# Picobot_10.net
KiCad netlist of a schematic drawn in EAGLE
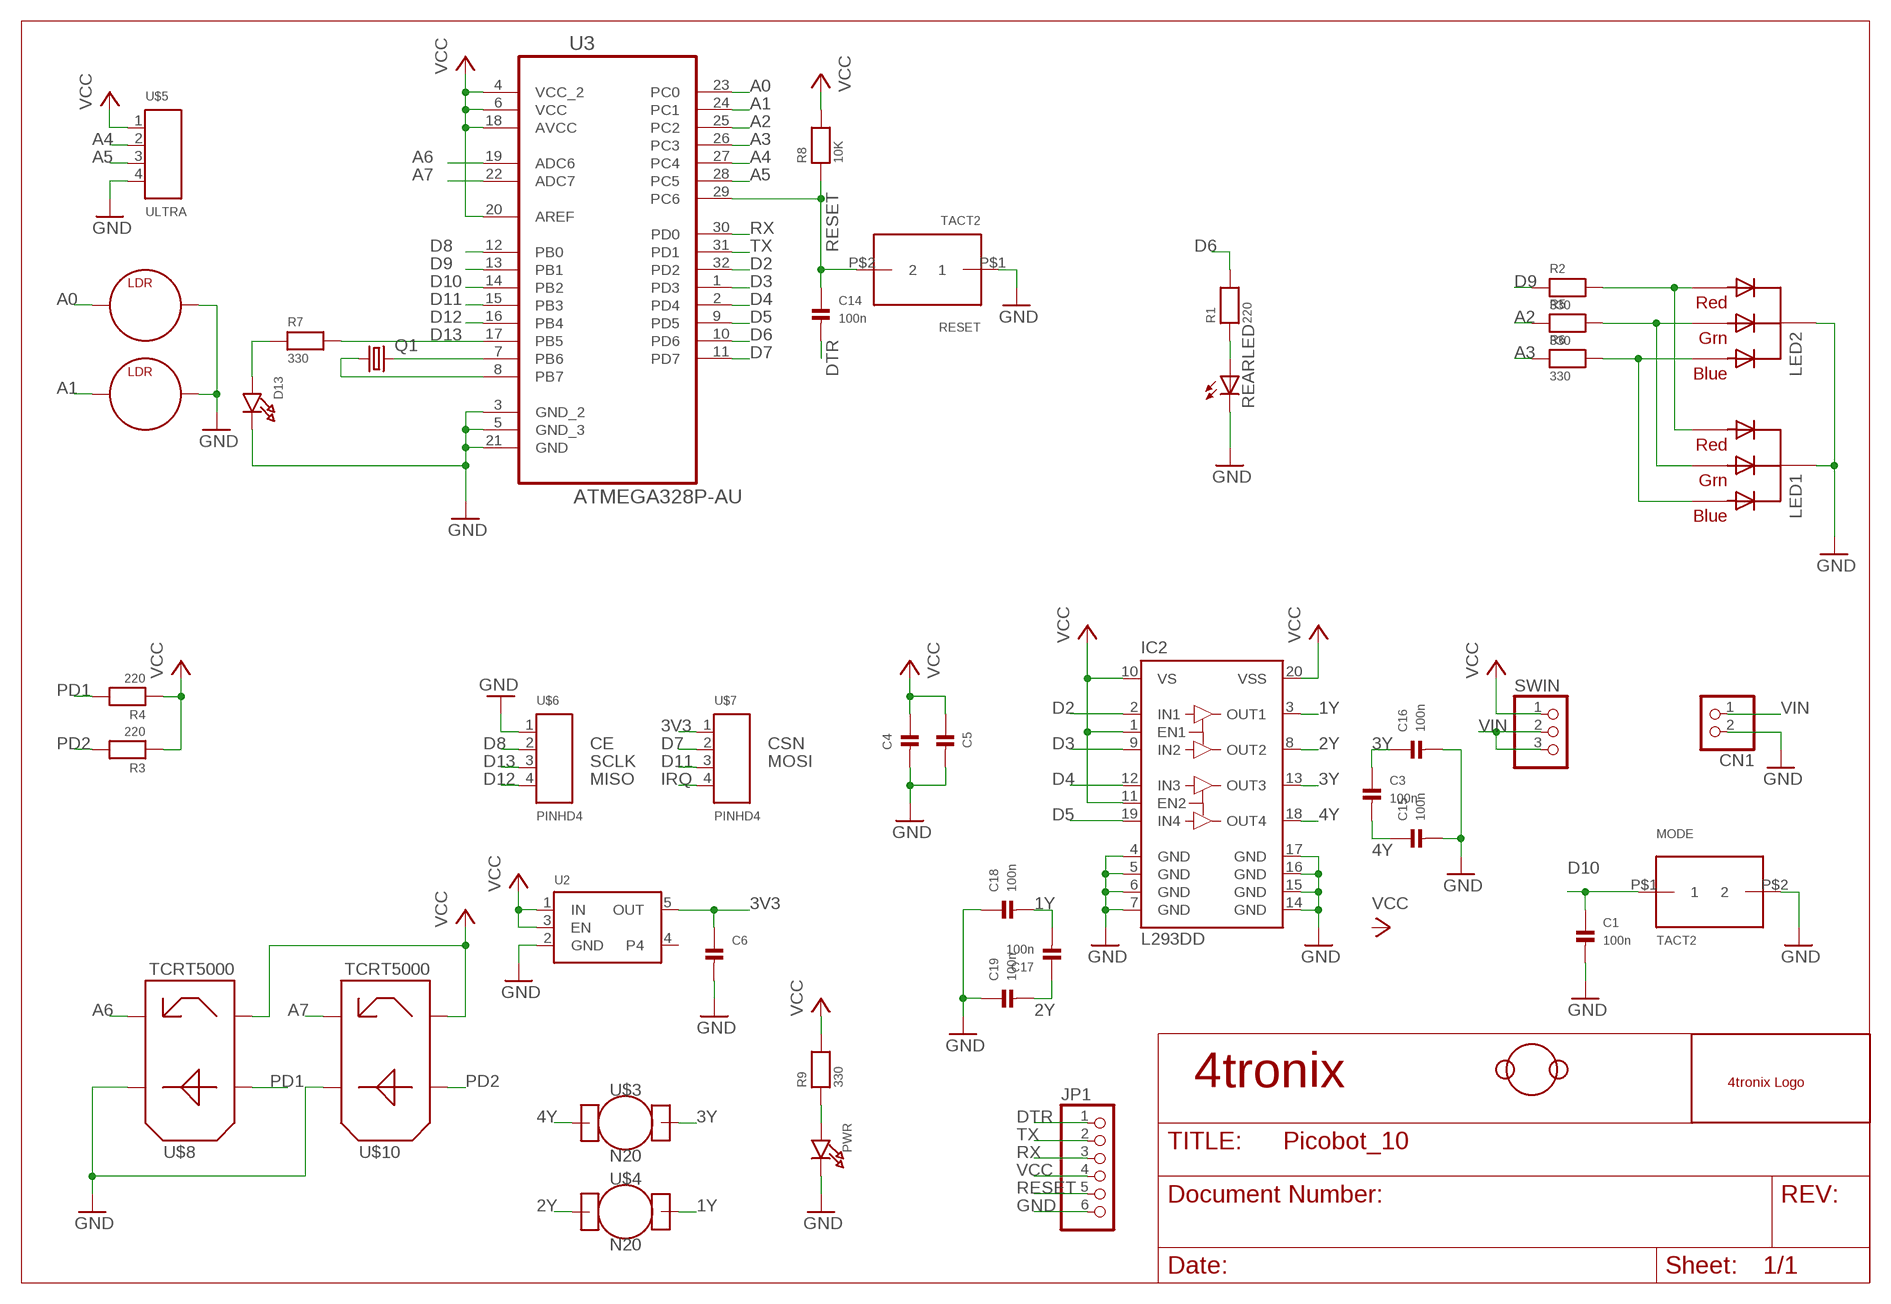
[diagram p0: schematic, sheet 1]

(export (version "E")
  (design (tool "Eeschema 10.0.6"))
  (components
    (comp (ref "C1")
      (value "100n")
      (footprint "eagle-import:_0805MP")
      (libsource (lib "eagle-import") (part "CAP_CERAMIC_0805MP"))
    )
    (comp (ref "C3")
      (value "100n")
      (footprint "eagle-import:_0805MP")
      (libsource (lib "eagle-import") (part "CAP_CERAMIC_0805MP"))
    )
    (comp (ref "C4")
      (value "CAP_CERAMIC_0805MP")
      (footprint "eagle-import:_0805MP")
      (libsource (lib "eagle-import") (part "CAP_CERAMIC_0805MP"))
    )
    (comp (ref "C5")
      (value "CAP_CERAMIC_0805MP")
      (footprint "eagle-import:_0805MP")
      (libsource (lib "eagle-import") (part "CAP_CERAMIC_0805MP"))
    )
    (comp (ref "C6")
      (value "CAP_CERAMIC_0805MP")
      (footprint "eagle-import:_0805MP")
      (libsource (lib "eagle-import") (part "CAP_CERAMIC_0805MP"))
    )
    (comp (ref "C14")
      (value "100n")
      (footprint "eagle-import:_0805MP")
      (libsource (lib "eagle-import") (part "CAP_CERAMIC_0805MP"))
    )
    (comp (ref "C15")
      (value "100n")
      (footprint "eagle-import:_0805MP")
      (libsource (lib "eagle-import") (part "CAP_CERAMIC_0805MP"))
    )
    (comp (ref "C16")
      (value "100n")
      (footprint "eagle-import:_0805MP")
      (libsource (lib "eagle-import") (part "CAP_CERAMIC_0805MP"))
    )
    (comp (ref "C17")
      (value "100n")
      (footprint "eagle-import:_0805MP")
      (libsource (lib "eagle-import") (part "CAP_CERAMIC_0805MP"))
    )
    (comp (ref "C18")
      (value "100n")
      (footprint "eagle-import:_0805MP")
      (libsource (lib "eagle-import") (part "CAP_CERAMIC_0805MP"))
    )
    (comp (ref "C19")
      (value "100n")
      (footprint "eagle-import:_0805MP")
      (libsource (lib "eagle-import") (part "CAP_CERAMIC_0805MP"))
    )
    (comp (ref "CN1")
      (value "JST_2PIN-THM")
      (footprint "eagle-import:JST-PH-2-THM")
      (libsource (lib "eagle-import") (part "JST_2PIN-THM"))
    )
    (comp (ref "D13")
      (value "LED0805_NOOUTLINE")
      (footprint "eagle-import:CHIPLED_0805_NOOUTLINE")
      (libsource (lib "eagle-import") (part "LED0805_NOOUTLINE"))
    )
    (comp (ref "IC2")
      (value "L293DD")
      (footprint "eagle-import:SO20")
      (libsource (lib "eagle-import") (part "L293DD"))
    )
    (comp (ref "JP1")
      (value "PINHD-1X6CB")
      (footprint "eagle-import:1X06-CLEANBIG")
      (libsource (lib "eagle-import") (part "PINHD-1X6CB"))
    )
    (comp (ref "LDR1")
      (value "LDR")
      (footprint "eagle-import:LDR")
      (libsource (lib "eagle-import") (part "LDR"))
    )
    (comp (ref "LDR2")
      (value "LDR")
      (footprint "eagle-import:LDR")
      (libsource (lib "eagle-import") (part "LDR"))
    )
    (comp (ref "LED1")
      (value "RGBLED_CA-5MM")
      (footprint "eagle-import:LED5MMRGB")
      (libsource (lib "eagle-import") (part "RGBLED_CA-5MM"))
    )
    (comp (ref "LED2")
      (value "RGBLED_CA-5MM")
      (footprint "eagle-import:LED5MMRGB")
      (libsource (lib "eagle-import") (part "RGBLED_CA-5MM"))
    )
    (comp (ref "MODE")
      (value "TACT2")
      (footprint "eagle-import:TACT2-PIN")
      (libsource (lib "eagle-import") (part "TACT2"))
    )
    (comp (ref "PWR")
      (value "LED0805_NOOUTLINE")
      (footprint "eagle-import:CHIPLED_0805_NOOUTLINE")
      (libsource (lib "eagle-import") (part "LED0805_NOOUTLINE"))
    )
    (comp (ref "Q1")
      (value "CRYSTALHC49S")
      (footprint "eagle-import:HC49_S")
      (libsource (lib "eagle-import") (part "CRYSTALHC49S"))
    )
    (comp (ref "R1")
      (value "220")
      (footprint "eagle-import:0805_NOTHERMALS")
      (libsource (lib "eagle-import") (part "RESISTOR0805_NOTHERMALS"))
    )
    (comp (ref "R2")
      (value "330")
      (footprint "eagle-import:0805_NOTHERMALS")
      (libsource (lib "eagle-import") (part "RESISTOR0805_NOTHERMALS"))
    )
    (comp (ref "R3")
      (value "220")
      (footprint "eagle-import:0805_NOTHERMALS")
      (libsource (lib "eagle-import") (part "RESISTOR0805_NOTHERMALS"))
    )
    (comp (ref "R4")
      (value "220")
      (footprint "eagle-import:0805_NOTHERMALS")
      (libsource (lib "eagle-import") (part "RESISTOR0805_NOTHERMALS"))
    )
    (comp (ref "R5")
      (value "330")
      (footprint "eagle-import:0805_NOTHERMALS")
      (libsource (lib "eagle-import") (part "RESISTOR0805_NOTHERMALS"))
    )
    (comp (ref "R6")
      (value "330")
      (footprint "eagle-import:0805_NOTHERMALS")
      (libsource (lib "eagle-import") (part "RESISTOR0805_NOTHERMALS"))
    )
    (comp (ref "R7")
      (value "330")
      (footprint "eagle-import:0805_NOTHERMALS")
      (libsource (lib "eagle-import") (part "RESISTOR0805_NOTHERMALS"))
    )
    (comp (ref "R8")
      (value "10K")
      (footprint "eagle-import:0805_NOTHERMALS")
      (libsource (lib "eagle-import") (part "RESISTOR0805_NOTHERMALS"))
    )
    (comp (ref "R9")
      (value "330")
      (footprint "eagle-import:0805_NOTHERMALS")
      (libsource (lib "eagle-import") (part "RESISTOR0805_NOTHERMALS"))
    )
    (comp (ref "REARLED")
      (value "LED3MM")
      (footprint "eagle-import:LED3MM")
      (libsource (lib "eagle-import") (part "LED3MM"))
    )
    (comp (ref "RESET")
      (value "TACT2")
      (footprint "eagle-import:TACT2-PIN")
      (libsource (lib "eagle-import") (part "TACT2"))
    )
    (comp (ref "SWIN")
      (value "PINHD-1X3CB")
      (footprint "eagle-import:1X03-CLEANBIG")
      (libsource (lib "eagle-import") (part "PINHD-1X3CB"))
    )
    (comp (ref "U$2")
      (value "LOGO")
      (footprint "eagle-import:LOGO")
      (libsource (lib "eagle-import") (part "LOGO"))
    )
    (comp (ref "U$3")
      (value "N20")
      (footprint "eagle-import:N20")
      (libsource (lib "eagle-import") (part "N20"))
    )
    (comp (ref "U$4")
      (value "N20")
      (footprint "eagle-import:N20")
      (libsource (lib "eagle-import") (part "N20"))
    )
    (comp (ref "U$5")
      (value "ULTRA")
      (footprint "eagle-import:PINHD4")
      (libsource (lib "eagle-import") (part "PINHD4"))
    )
    (comp (ref "U$6")
      (value "PINHD4")
      (footprint "eagle-import:PINHD4")
      (libsource (lib "eagle-import") (part "PINHD4"))
    )
    (comp (ref "U$7")
      (value "PINHD4")
      (footprint "eagle-import:PINHD4")
      (libsource (lib "eagle-import") (part "PINHD4"))
    )
    (comp (ref "U$8")
      (value "TCRT5000")
      (footprint "eagle-import:TCRT5000")
      (libsource (lib "eagle-import") (part "TCRT5000"))
    )
    (comp (ref "U$9")
      (value "DFRBALL")
      (footprint "eagle-import:DFRBALL")
      (libsource (lib "eagle-import") (part "DFRBALL"))
    )
    (comp (ref "U$10")
      (value "TCRT5000")
      (footprint "eagle-import:TCRT5000")
      (libsource (lib "eagle-import") (part "TCRT5000"))
    )
    (comp (ref "U2")
      (value "VREG_SOT23-5")
      (footprint "eagle-import:SOT23-5")
      (libsource (lib "eagle-import") (part "VREG_SOT23-5"))
    )
    (comp (ref "U3")
      (value "ATMEGA328P-AU")
      (footprint "eagle-import:QFP80P900X900X120-32N")
      (libsource (lib "eagle-import") (part "ATMEGA328P-AU"))
    )
  )
  (nets
    (net (code "1") (name "/1Y") (class "Default")
      (node (ref "C17") (pin "2") (pinfunction "P$2_2") (pintype "passive"))
      (node (ref "C18") (pin "2") (pinfunction "P$2_2") (pintype "passive"))
      (node (ref "IC2") (pin "3") (pinfunction "OUT1_3") (pintype "output"))
      (node (ref "U$4") (pin "MTRA") (pinfunction "MTRB_MTRA") (pintype "bidirectional"))
    )
    (net (code "2") (name "/2Y") (class "Default")
      (node (ref "C17") (pin "1") (pinfunction "P$1_1") (pintype "passive"))
      (node (ref "C19") (pin "2") (pinfunction "P$2_2") (pintype "passive"))
      (node (ref "IC2") (pin "8") (pinfunction "OUT2_8") (pintype "output"))
      (node (ref "U$4") (pin "MTRB") (pinfunction "MTRA_MTRB") (pintype "bidirectional"))
    )
    (net (code "3") (name "/3V3") (class "Default")
      (node (ref "C6") (pin "1") (pinfunction "P$1_1") (pintype "passive"))
      (node (ref "U$7") (pin "1") (pinfunction "1_1") (pintype "bidirectional"))
      (node (ref "U2") (pin "5") (pinfunction "OUT_5") (pintype "bidirectional"))
    )
    (net (code "4") (name "/3Y") (class "Default")
      (node (ref "C16") (pin "1") (pinfunction "P$1_1") (pintype "passive"))
      (node (ref "C3") (pin "1") (pinfunction "P$1_1") (pintype "passive"))
      (node (ref "IC2") (pin "13") (pinfunction "OUT3_13") (pintype "output"))
      (node (ref "U$3") (pin "MTRA") (pinfunction "MTRB_MTRA") (pintype "bidirectional"))
    )
    (net (code "5") (name "/4Y") (class "Default")
      (node (ref "C15") (pin "1") (pinfunction "P$1_1") (pintype "passive"))
      (node (ref "C3") (pin "2") (pinfunction "P$2_2") (pintype "passive"))
      (node (ref "IC2") (pin "18") (pinfunction "OUT4_18") (pintype "output"))
      (node (ref "U$3") (pin "MTRB") (pinfunction "MTRA_MTRB") (pintype "bidirectional"))
    )
    (net (code "6") (name "/A0") (class "Default")
      (node (ref "LDR1") (pin "A") (pinfunction "P$1_A") (pintype "bidirectional"))
      (node (ref "U3") (pin "23") (pinfunction "PC0_23") (pintype "bidirectional"))
    )
    (net (code "7") (name "/A1") (class "Default")
      (node (ref "LDR2") (pin "A") (pinfunction "P$1_A") (pintype "bidirectional"))
      (node (ref "U3") (pin "24") (pinfunction "PC1_24") (pintype "bidirectional"))
    )
    (net (code "8") (name "/A2") (class "Default")
      (node (ref "R5") (pin "1") (pinfunction "1_1") (pintype "passive"))
      (node (ref "U3") (pin "25") (pinfunction "PC2_25") (pintype "bidirectional"))
    )
    (net (code "9") (name "/A3") (class "Default")
      (node (ref "R6") (pin "1") (pinfunction "1_1") (pintype "passive"))
      (node (ref "U3") (pin "26") (pinfunction "PC3_26") (pintype "bidirectional"))
    )
    (net (code "10") (name "/A4") (class "Default")
      (node (ref "U$5") (pin "2") (pinfunction "2_2") (pintype "bidirectional"))
      (node (ref "U3") (pin "27") (pinfunction "PC4_27") (pintype "bidirectional"))
    )
    (net (code "11") (name "/A5") (class "Default")
      (node (ref "U$5") (pin "3") (pinfunction "3_3") (pintype "bidirectional"))
      (node (ref "U3") (pin "28") (pinfunction "PC5_28") (pintype "bidirectional"))
    )
    (net (code "12") (name "/A6") (class "Default")
      (node (ref "U$8") (pin "TR2") (pinfunction "TR2_TR2") (pintype "bidirectional"))
      (node (ref "U3") (pin "19") (pinfunction "ADC6_19") (pintype "input"))
    )
    (net (code "13") (name "/A7") (class "Default")
      (node (ref "U$10") (pin "TR2") (pinfunction "TR2_TR2") (pintype "bidirectional"))
      (node (ref "U3") (pin "22") (pinfunction "ADC7_22") (pintype "input"))
    )
    (net (code "14") (name "/D2") (class "Default")
      (node (ref "IC2") (pin "2") (pinfunction "IN1_2") (pintype "input"))
      (node (ref "U3") (pin "32") (pinfunction "PD2_32") (pintype "bidirectional"))
    )
    (net (code "15") (name "/D3") (class "Default")
      (node (ref "IC2") (pin "9") (pinfunction "IN2_9") (pintype "input"))
      (node (ref "U3") (pin "1") (pinfunction "PD3_1") (pintype "bidirectional"))
    )
    (net (code "16") (name "/D4") (class "Default")
      (node (ref "IC2") (pin "12") (pinfunction "IN3_12") (pintype "input"))
      (node (ref "U3") (pin "2") (pinfunction "PD4_2") (pintype "bidirectional"))
    )
    (net (code "17") (name "/D5") (class "Default")
      (node (ref "IC2") (pin "19") (pinfunction "IN4_19") (pintype "input"))
      (node (ref "U3") (pin "9") (pinfunction "PD5_9") (pintype "bidirectional"))
    )
    (net (code "18") (name "/D6") (class "Default")
      (node (ref "R1") (pin "2") (pinfunction "2_2") (pintype "passive"))
      (node (ref "U3") (pin "10") (pinfunction "PD6_10") (pintype "bidirectional"))
    )
    (net (code "19") (name "/D7") (class "Default")
      (node (ref "U$7") (pin "2") (pinfunction "2_2") (pintype "bidirectional"))
      (node (ref "U3") (pin "11") (pinfunction "PD7_11") (pintype "bidirectional"))
    )
    (net (code "20") (name "/D8") (class "Default")
      (node (ref "U$6") (pin "2") (pinfunction "2_2") (pintype "bidirectional"))
      (node (ref "U3") (pin "12") (pinfunction "PB0_12") (pintype "bidirectional"))
    )
    (net (code "21") (name "/D9") (class "Default")
      (node (ref "R2") (pin "1") (pinfunction "1_1") (pintype "passive"))
      (node (ref "U3") (pin "13") (pinfunction "PB1_13") (pintype "bidirectional"))
    )
    (net (code "22") (name "/D10") (class "Default")
      (node (ref "C1") (pin "1") (pinfunction "P$1_1") (pintype "passive"))
      (node (ref "MODE") (pin "P$1") (pinfunction "1_P$1") (pintype "bidirectional"))
      (node (ref "U3") (pin "14") (pinfunction "PB2_14") (pintype "bidirectional"))
    )
    (net (code "23") (name "/D11") (class "Default")
      (node (ref "U$7") (pin "3") (pinfunction "3_3") (pintype "bidirectional"))
      (node (ref "U3") (pin "15") (pinfunction "PB3_15") (pintype "bidirectional"))
    )
    (net (code "24") (name "/D12") (class "Default")
      (node (ref "U$6") (pin "4") (pinfunction "4_4") (pintype "bidirectional"))
      (node (ref "U3") (pin "16") (pinfunction "PB4_16") (pintype "bidirectional"))
    )
    (net (code "25") (name "/D13") (class "Default")
      (node (ref "R7") (pin "2") (pinfunction "2_2") (pintype "passive"))
      (node (ref "U$6") (pin "3") (pinfunction "3_3") (pintype "bidirectional"))
      (node (ref "U3") (pin "17") (pinfunction "PB5_17") (pintype "bidirectional"))
    )
    (net (code "26") (name "/DTR") (class "Default")
      (node (ref "C14") (pin "2") (pinfunction "P$2_2") (pintype "passive"))
      (node (ref "JP1") (pin "1") (pinfunction "1_1") (pintype "passive"))
    )
    (net (code "27") (name "/IRQ") (class "Default")
      (node (ref "U$7") (pin "4") (pinfunction "4_4") (pintype "bidirectional"))
    )
    (net (code "28") (name "/PD1") (class "Default")
      (node (ref "R4") (pin "2") (pinfunction "2_2") (pintype "passive"))
      (node (ref "U$8") (pin "LED1") (pinfunction "LED1_LED1") (pintype "bidirectional"))
    )
    (net (code "29") (name "/PD2") (class "Default")
      (node (ref "R3") (pin "2") (pinfunction "2_2") (pintype "passive"))
      (node (ref "U$10") (pin "LED1") (pinfunction "LED1_LED1") (pintype "bidirectional"))
    )
    (net (code "30") (name "/RESET") (class "Default")
      (node (ref "C14") (pin "1") (pinfunction "P$1_1") (pintype "passive"))
      (node (ref "JP1") (pin "5") (pinfunction "5_5") (pintype "passive"))
      (node (ref "R8") (pin "1") (pinfunction "1_1") (pintype "passive"))
      (node (ref "RESET") (pin "P$2") (pinfunction "2_P$2") (pintype "bidirectional"))
      (node (ref "U3") (pin "29") (pinfunction "PC6_29") (pintype "bidirectional"))
    )
    (net (code "31") (name "/RX") (class "Default")
      (node (ref "JP1") (pin "3") (pinfunction "3_3") (pintype "passive"))
      (node (ref "U3") (pin "30") (pinfunction "PD0_30") (pintype "bidirectional"))
    )
    (net (code "32") (name "/TX") (class "Default")
      (node (ref "JP1") (pin "2") (pinfunction "2_2") (pintype "passive"))
      (node (ref "U3") (pin "31") (pinfunction "PD1_31") (pintype "bidirectional"))
    )
    (net (code "33") (name "/VIN") (class "Default")
      (node (ref "CN1") (pin "1") (pinfunction "2_1") (pintype "passive"))
      (node (ref "SWIN") (pin "2") (pinfunction "2_2") (pintype "passive"))
      (node (ref "SWIN") (pin "3") (pinfunction "3_3") (pintype "passive"))
    )
    (net (code "34") (name "GND") (class "Default")
      (node (ref "C1") (pin "2") (pinfunction "P$2_2") (pintype "passive"))
      (node (ref "C15") (pin "2") (pinfunction "P$2_2") (pintype "passive"))
      (node (ref "C16") (pin "2") (pinfunction "P$2_2") (pintype "passive"))
      (node (ref "C18") (pin "1") (pinfunction "P$1_1") (pintype "passive"))
      (node (ref "C19") (pin "1") (pinfunction "P$1_1") (pintype "passive"))
      (node (ref "C4") (pin "2") (pinfunction "P$2_2") (pintype "passive"))
      (node (ref "C5") (pin "2") (pinfunction "P$2_2") (pintype "passive"))
      (node (ref "C6") (pin "2") (pinfunction "P$2_2") (pintype "passive"))
      (node (ref "CN1") (pin "2") (pinfunction "1_2") (pintype "passive"))
      (node (ref "D13") (pin "C") (pinfunction "C_C") (pintype "passive"))
      (node (ref "IC2") (pin "14") (pinfunction "GND_14") (pintype "power_in"))
      (node (ref "IC2") (pin "15") (pinfunction "GND_15") (pintype "power_in"))
      (node (ref "IC2") (pin "16") (pinfunction "GND_16") (pintype "power_in"))
      (node (ref "IC2") (pin "17") (pinfunction "GND_17") (pintype "power_in"))
      (node (ref "IC2") (pin "4") (pinfunction "GND_4") (pintype "power_in"))
      (node (ref "IC2") (pin "5") (pinfunction "GND_5") (pintype "power_in"))
      (node (ref "IC2") (pin "6") (pinfunction "GND_6") (pintype "power_in"))
      (node (ref "IC2") (pin "7") (pinfunction "GND_7") (pintype "power_in"))
      (node (ref "JP1") (pin "6") (pinfunction "6_6") (pintype "passive"))
      (node (ref "LDR1") (pin "K") (pinfunction "P$2_K") (pintype "bidirectional"))
      (node (ref "LDR2") (pin "K") (pinfunction "P$2_K") (pintype "bidirectional"))
      (node (ref "LED1") (pin "2") (pinfunction "VCC_2") (pintype "bidirectional"))
      (node (ref "LED2") (pin "2") (pinfunction "VCC_2") (pintype "bidirectional"))
      (node (ref "MODE") (pin "P$2") (pinfunction "2_P$2") (pintype "bidirectional"))
      (node (ref "PWR") (pin "C") (pinfunction "C_C") (pintype "passive"))
      (node (ref "REARLED") (pin "K") (pinfunction "C_K") (pintype "passive"))
      (node (ref "RESET") (pin "P$1") (pinfunction "1_P$1") (pintype "bidirectional"))
      (node (ref "U$10") (pin "LED2") (pinfunction "LED2_LED2") (pintype "bidirectional"))
      (node (ref "U$5") (pin "4") (pinfunction "4_4") (pintype "bidirectional"))
      (node (ref "U$6") (pin "1") (pinfunction "1_1") (pintype "bidirectional"))
      (node (ref "U$8") (pin "LED2") (pinfunction "LED2_LED2") (pintype "bidirectional"))
      (node (ref "U2") (pin "2") (pinfunction "GND_2") (pintype "bidirectional"))
      (node (ref "U3") (pin "21") (pinfunction "GND_21") (pintype "passive"))
      (node (ref "U3") (pin "3") (pinfunction "GND_2_3") (pintype "passive"))
      (node (ref "U3") (pin "5") (pinfunction "GND_3_5") (pintype "passive"))
    )
    (net (code "35") (name "Net-(D13-PadA)") (class "Default")
      (node (ref "D13") (pin "A") (pinfunction "A_A") (pintype "passive"))
      (node (ref "R7") (pin "1") (pinfunction "1_1") (pintype "passive"))
    )
    (net (code "36") (name "Net-(LED1-BLUE)") (class "Default")
      (node (ref "LED1") (pin "4") (pinfunction "BLUE_4") (pintype "bidirectional"))
      (node (ref "LED2") (pin "4") (pinfunction "BLUE_4") (pintype "bidirectional"))
      (node (ref "R6") (pin "2") (pinfunction "2_2") (pintype "passive"))
    )
    (net (code "37") (name "Net-(LED1-GREEN)") (class "Default")
      (node (ref "LED1") (pin "3") (pinfunction "GREEN_3") (pintype "bidirectional"))
      (node (ref "LED2") (pin "3") (pinfunction "GREEN_3") (pintype "bidirectional"))
      (node (ref "R5") (pin "2") (pinfunction "2_2") (pintype "passive"))
    )
    (net (code "38") (name "Net-(LED1-RED)") (class "Default")
      (node (ref "LED1") (pin "1") (pinfunction "RED_1") (pintype "bidirectional"))
      (node (ref "LED2") (pin "1") (pinfunction "RED_1") (pintype "bidirectional"))
      (node (ref "R2") (pin "2") (pinfunction "2_2") (pintype "passive"))
    )
    (net (code "39") (name "Net-(PWR-PadA)") (class "Default")
      (node (ref "PWR") (pin "A") (pinfunction "A_A") (pintype "passive"))
      (node (ref "R9") (pin "1") (pinfunction "1_1") (pintype "passive"))
    )
    (net (code "40") (name "Net-(R1-Pad1)") (class "Default")
      (node (ref "R1") (pin "1") (pinfunction "1_1") (pintype "passive"))
      (node (ref "REARLED") (pin "A") (pinfunction "A_A") (pintype "passive"))
    )
    (net (code "41") (name "Net-(U3-PB6)") (class "Default")
      (node (ref "Q1") (pin "2") (pinfunction "2_2") (pintype "passive"))
      (node (ref "U3") (pin "7") (pinfunction "PB6_7") (pintype "bidirectional"))
    )
    (net (code "42") (name "Net-(U3-PB7)") (class "Default")
      (node (ref "Q1") (pin "1") (pinfunction "1_1") (pintype "passive"))
      (node (ref "U3") (pin "8") (pinfunction "PB7_8") (pintype "bidirectional"))
    )
    (net (code "43") (name "VCC") (class "Default")
      (node (ref "C4") (pin "1") (pinfunction "P$1_1") (pintype "passive"))
      (node (ref "C5") (pin "1") (pinfunction "P$1_1") (pintype "passive"))
      (node (ref "IC2") (pin "1") (pinfunction "EN1_1") (pintype "input"))
      (node (ref "IC2") (pin "10") (pinfunction "VS_10") (pintype "power_in"))
      (node (ref "IC2") (pin "11") (pinfunction "EN2_11") (pintype "input"))
      (node (ref "IC2") (pin "20") (pinfunction "VSS_20") (pintype "power_in"))
      (node (ref "JP1") (pin "4") (pinfunction "4_4") (pintype "passive"))
      (node (ref "R3") (pin "1") (pinfunction "1_1") (pintype "passive"))
      (node (ref "R4") (pin "1") (pinfunction "1_1") (pintype "passive"))
      (node (ref "R8") (pin "2") (pinfunction "2_2") (pintype "passive"))
      (node (ref "R9") (pin "2") (pinfunction "2_2") (pintype "passive"))
      (node (ref "SWIN") (pin "1") (pinfunction "1_1") (pintype "passive"))
      (node (ref "U$10") (pin "TR1") (pinfunction "TR1_TR1") (pintype "bidirectional"))
      (node (ref "U$5") (pin "1") (pinfunction "1_1") (pintype "bidirectional"))
      (node (ref "U$8") (pin "TR1") (pinfunction "TR1_TR1") (pintype "bidirectional"))
      (node (ref "U2") (pin "1") (pinfunction "IN_1") (pintype "bidirectional"))
      (node (ref "U2") (pin "3") (pinfunction "EN_3") (pintype "bidirectional"))
      (node (ref "U3") (pin "18") (pinfunction "AVCC_18") (pintype "power_in"))
      (node (ref "U3") (pin "20") (pinfunction "AREF_20") (pintype "input"))
      (node (ref "U3") (pin "4") (pinfunction "VCC_2_4") (pintype "power_in"))
      (node (ref "U3") (pin "6") (pinfunction "VCC_6") (pintype "power_in"))
    )
    (net (code "44") (name "unconnected-(U2-P4-Pad4)") (class "Default")
      (node (ref "U2") (pin "4") (pinfunction "P4_4") (pintype "bidirectional"))
    )
  )
)
